# Sheet_FS8626.net
KiCad netlist of a schematic drawn in Altium Designer
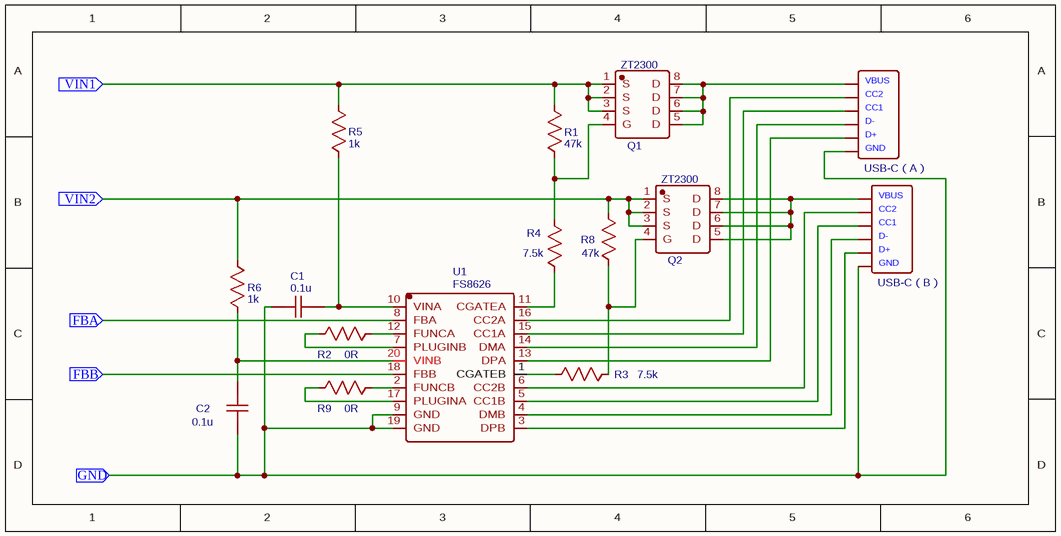
[diagram p0: Sheet_FS8626.schdoc]

(export (version "E")
  (design (tool "Eeschema 10.0.6"))
  (components
    (comp (ref "C1")
      (value "0.1u")
      (footprint "C0603")
      (fields (field (name "CONTRIBUTOR") "LCEDA_Lib"))
      (libsource (lib "altium-import") (part "root_0_0.1u_"))
    )
    (comp (ref "C2")
      (value "0.1u")
      (footprint "C0603")
      (fields (field (name "CONTRIBUTOR") "LCEDA_Lib"))
      (libsource (lib "altium-import") (part "root_1_0.1u_"))
    )
    (comp (ref "Q1")
      (value "ZT2300")
      (footprint "DFN3X3-8L")
      (fields
        (field (name "MANUFACTURER") "VBsemi Elec")
        (field (name "MANUFACTURER PART") "NCE3035G")
        (field (name "CONTRIBUTOR") "LCSC")
      )
      (libsource (lib "altium-import") (part "root_0_ZT2300_"))
    )
    (comp (ref "Q2")
      (value "ZT2300")
      (footprint "DFN3X3-8L")
      (fields
        (field (name "MANUFACTURER") "VBsemi Elec")
        (field (name "MANUFACTURER PART") "NCE3035G")
        (field (name "CONTRIBUTOR") "LCSC")
      )
      (libsource (lib "altium-import") (part "root_0_ZT2300_"))
    )
    (comp (ref "R1")
      (value "47k")
      (footprint "R0603")
      (fields (field (name "CONTRIBUTOR") "LCEDA_Lib"))
      (libsource (lib "altium-import") (part "root_1_47k_"))
    )
    (comp (ref "R2")
      (value "0R")
      (footprint "R0603")
      (fields (field (name "CONTRIBUTOR") "LCEDA_Lib"))
      (libsource (lib "altium-import") (part "root_0_0R_"))
    )
    (comp (ref "R3")
      (value "7.5k")
      (footprint "R0603")
      (fields (field (name "CONTRIBUTOR") "LCEDA_Lib"))
      (libsource (lib "altium-import") (part "root_0_7.5k_"))
    )
    (comp (ref "R4")
      (value "7.5k")
      (footprint "R0603")
      (fields (field (name "CONTRIBUTOR") "LCEDA_Lib"))
      (libsource (lib "altium-import") (part "root_1_7.5k_"))
    )
    (comp (ref "R5")
      (value "1k")
      (footprint "R1206")
      (fields (field (name "CONTRIBUTOR") "LCEDA_Lib"))
      (libsource (lib "altium-import") (part "root_1_1k_"))
    )
    (comp (ref "R6")
      (value "1k")
      (footprint "R1206")
      (fields (field (name "CONTRIBUTOR") "LCEDA_Lib"))
      (libsource (lib "altium-import") (part "root_1_1k_"))
    )
    (comp (ref "R8")
      (value "47k")
      (footprint "R0603")
      (fields (field (name "CONTRIBUTOR") "LCEDA_Lib"))
      (libsource (lib "altium-import") (part "root_1_47k_"))
    )
    (comp (ref "R9")
      (value "0R")
      (footprint "R0603")
      (fields (field (name "CONTRIBUTOR") "LCEDA_Lib"))
      (libsource (lib "altium-import") (part "root_0_0R_"))
    )
    (comp (ref "U1")
      (value "FS8626")
      (footprint "ETSSOP20_L6.5-W4.4-P0.65-LS6.4-BL")
      (fields
        (field (name "MANUFACTURER") "TI(德州仪器)")
        (field (name "MANUFACTURER PART") "PCF8574APWR")
        (field (name "CONTRIBUTOR") "LCSC")
      )
      (libsource (lib "altium-import") (part "root_0_FS8626_"))
    )
    (comp (ref "U2")
      (value "USB-C（B）")
      (footprint "FCQFN-15L_L3.0-W3.0-P0.50-BL_SCT63140FMAR")
      (fields
        (field (name "MANUFACTURER") "SCT")
        (field (name "MANUFACTURER PART") "SCT63140FMAR")
        (field (name "CONTRIBUTOR") "TaoPatrick")
      )
      (libsource (lib "altium-import") (part "root_0_USB-C（B）_"))
    )
    (comp (ref "U3")
      (value "USB-C（A）")
      (footprint "FCQFN-15L_L3.0-W3.0-P0.50-BL_SCT63140FMAR")
      (fields
        (field (name "MANUFACTURER") "SCT")
        (field (name "MANUFACTURER PART") "SCT63140FMAR")
        (field (name "CONTRIBUTOR") "TaoPatrick")
      )
      (libsource (lib "altium-import") (part "root_0_USB-C（A）_"))
    )
  )
  (nets
    (net (code "1") (name "/FBA") (class "Default")
      (node (ref "U1") (pin "8") (pinfunction "FBA_8") (pintype "passive"))
    )
    (net (code "2") (name "/FBB") (class "Default")
      (node (ref "U1") (pin "18") (pinfunction "FBB_18") (pintype "passive"))
    )
    (net (code "3") (name "/GND") (class "Default")
      (node (ref "C1") (pin "1") (pinfunction "1_1") (pintype "passive"))
      (node (ref "C2") (pin "1") (pinfunction "1_1") (pintype "passive"))
      (node (ref "U1") (pin "19") (pinfunction "GND_19") (pintype "passive"))
      (node (ref "U1") (pin "9") (pinfunction "GND_9") (pintype "passive"))
    )
    (net (code "4") (name "/VIN1") (class "Default")
      (node (ref "Q1") (pin "1") (pinfunction "S_1") (pintype "passive"))
      (node (ref "Q1") (pin "2") (pinfunction "S_2") (pintype "passive"))
      (node (ref "Q1") (pin "3") (pinfunction "S_3") (pintype "passive"))
      (node (ref "R1") (pin "2") (pinfunction "2_2") (pintype "passive"))
      (node (ref "R5") (pin "2") (pinfunction "2_2") (pintype "passive"))
    )
    (net (code "5") (name "/VIN2") (class "Default")
      (node (ref "Q2") (pin "1") (pinfunction "S_1") (pintype "passive"))
      (node (ref "Q2") (pin "2") (pinfunction "S_2") (pintype "passive"))
      (node (ref "Q2") (pin "3") (pinfunction "S_3") (pintype "passive"))
      (node (ref "R6") (pin "2") (pinfunction "2_2") (pintype "passive"))
      (node (ref "R8") (pin "2") (pinfunction "2_2") (pintype "passive"))
    )
    (net (code "6") (name "Net-(Q1-D-Pad5)") (class "Default")
      (node (ref "Q1") (pin "5") (pinfunction "D_5") (pintype "passive"))
      (node (ref "Q1") (pin "6") (pinfunction "D_6") (pintype "passive"))
      (node (ref "Q1") (pin "7") (pinfunction "D_7") (pintype "passive"))
      (node (ref "Q1") (pin "8") (pinfunction "D_8") (pintype "passive"))
    )
    (net (code "7") (name "Net-(Q1-G)") (class "Default")
      (node (ref "Q1") (pin "4") (pinfunction "G_4") (pintype "passive"))
      (node (ref "R1") (pin "1") (pinfunction "1_1") (pintype "passive"))
      (node (ref "R4") (pin "2") (pinfunction "2_2") (pintype "passive"))
    )
    (net (code "8") (name "Net-(Q2-D-Pad5)") (class "Default")
      (node (ref "Q2") (pin "5") (pinfunction "D_5") (pintype "passive"))
      (node (ref "Q2") (pin "6") (pinfunction "D_6") (pintype "passive"))
      (node (ref "Q2") (pin "7") (pinfunction "D_7") (pintype "passive"))
      (node (ref "Q2") (pin "8") (pinfunction "D_8") (pintype "passive"))
    )
    (net (code "9") (name "Net-(Q2-G)") (class "Default")
      (node (ref "Q2") (pin "4") (pinfunction "G_4") (pintype "passive"))
      (node (ref "R3") (pin "2") (pinfunction "2_2") (pintype "passive"))
      (node (ref "R8") (pin "1") (pinfunction "1_1") (pintype "passive"))
    )
    (net (code "10") (name "Net-(U1-CGATEA)") (class "Default")
      (node (ref "R4") (pin "1") (pinfunction "1_1") (pintype "passive"))
      (node (ref "U1") (pin "11") (pinfunction "CGATEA_11") (pintype "passive"))
    )
    (net (code "11") (name "Net-(U1-CGATEB)") (class "Default")
      (node (ref "R3") (pin "1") (pinfunction "1_1") (pintype "passive"))
      (node (ref "U1") (pin "1") (pinfunction "CGATEB_1") (pintype "passive"))
    )
    (net (code "12") (name "Net-(U1-FUNCA)") (class "Default")
      (node (ref "R2") (pin "2") (pinfunction "2_2") (pintype "passive"))
      (node (ref "U1") (pin "12") (pinfunction "FUNCA_12") (pintype "passive"))
    )
    (net (code "13") (name "Net-(U1-FUNCB)") (class "Default")
      (node (ref "R9") (pin "2") (pinfunction "2_2") (pintype "passive"))
      (node (ref "U1") (pin "2") (pinfunction "FUNCB_2") (pintype "passive"))
    )
    (net (code "14") (name "Net-(U1-PLUGINA)") (class "Default")
      (node (ref "R9") (pin "1") (pinfunction "1_1") (pintype "passive"))
      (node (ref "U1") (pin "17") (pinfunction "PLUGINA_17") (pintype "passive"))
    )
    (net (code "15") (name "Net-(U1-PLUGINB)") (class "Default")
      (node (ref "R2") (pin "1") (pinfunction "1_1") (pintype "passive"))
      (node (ref "U1") (pin "7") (pinfunction "PLUGINB_7") (pintype "passive"))
    )
    (net (code "16") (name "Net-(U1-VINA)") (class "Default")
      (node (ref "C1") (pin "2") (pinfunction "2_2") (pintype "passive"))
      (node (ref "R5") (pin "1") (pinfunction "1_1") (pintype "passive"))
      (node (ref "U1") (pin "10") (pinfunction "VINA_10") (pintype "passive"))
    )
    (net (code "17") (name "Net-(U1-VINB)") (class "Default")
      (node (ref "C2") (pin "2") (pinfunction "2_2") (pintype "passive"))
      (node (ref "R6") (pin "1") (pinfunction "1_1") (pintype "passive"))
      (node (ref "U1") (pin "20") (pinfunction "VINB_20") (pintype "passive"))
    )
    (net (code "18") (name "unconnected-(U1-CC1A-Pad15)") (class "Default")
      (node (ref "U1") (pin "15") (pinfunction "CC1A_15") (pintype "passive"))
    )
    (net (code "19") (name "unconnected-(U1-CC1B-Pad5)") (class "Default")
      (node (ref "U1") (pin "5") (pinfunction "CC1B_5") (pintype "passive"))
    )
    (net (code "20") (name "unconnected-(U1-CC2A-Pad16)") (class "Default")
      (node (ref "U1") (pin "16") (pinfunction "CC2A_16") (pintype "passive"))
    )
    (net (code "21") (name "unconnected-(U1-CC2B-Pad6)") (class "Default")
      (node (ref "U1") (pin "6") (pinfunction "CC2B_6") (pintype "passive"))
    )
    (net (code "22") (name "unconnected-(U1-DMA-Pad14)") (class "Default")
      (node (ref "U1") (pin "14") (pinfunction "DMA_14") (pintype "passive"))
    )
    (net (code "23") (name "unconnected-(U1-DMB-Pad4)") (class "Default")
      (node (ref "U1") (pin "4") (pinfunction "DMB_4") (pintype "passive"))
    )
    (net (code "24") (name "unconnected-(U1-DPA-Pad13)") (class "Default")
      (node (ref "U1") (pin "13") (pinfunction "DPA_13") (pintype "passive"))
    )
    (net (code "25") (name "unconnected-(U1-DPB-Pad3)") (class "Default")
      (node (ref "U1") (pin "3") (pinfunction "DPB_3") (pintype "passive"))
    )
    (net (code "26") (name "unconnected-(U2-SHELD-Pad2)") (class "Default")
      (node (ref "U2") (pin "2") (pinfunction "SHELD_2") (pintype "passive"))
    )
    (net (code "27") (name "unconnected-(U2-SHELD-Pad3)") (class "Default")
      (node (ref "U2") (pin "3") (pinfunction "SHELD_3") (pintype "passive"))
    )
    (net (code "28") (name "unconnected-(U2-SHELD-Pad4)") (class "Default")
      (node (ref "U2") (pin "4") (pinfunction "SHELD_4") (pintype "passive"))
    )
    (net (code "29") (name "unconnected-(U2-SHELD-Pad5)") (class "Default")
      (node (ref "U2") (pin "5") (pinfunction "SHELD_5") (pintype "passive"))
    )
    (net (code "30") (name "unconnected-(U2-SHELD-Pad5)_1") (class "Default")
      (node (ref "U2") (pin "5") (pinfunction "SHELD_5") (pintype "passive"))
    )
    (net (code "31") (name "unconnected-(U2-SHELD-Pad6)") (class "Default")
      (node (ref "U2") (pin "6") (pinfunction "SHELD_6") (pintype "passive"))
    )
    (net (code "32") (name "unconnected-(U3-SHELD-Pad2)") (class "Default")
      (node (ref "U3") (pin "2") (pinfunction "SHELD_2") (pintype "passive"))
    )
    (net (code "33") (name "unconnected-(U3-SHELD-Pad3)") (class "Default")
      (node (ref "U3") (pin "3") (pinfunction "SHELD_3") (pintype "passive"))
    )
    (net (code "34") (name "unconnected-(U3-SHELD-Pad4)") (class "Default")
      (node (ref "U3") (pin "4") (pinfunction "SHELD_4") (pintype "passive"))
    )
    (net (code "35") (name "unconnected-(U3-SHELD-Pad5)") (class "Default")
      (node (ref "U3") (pin "5") (pinfunction "SHELD_5") (pintype "passive"))
    )
    (net (code "36") (name "unconnected-(U3-SHELD-Pad5)_1") (class "Default")
      (node (ref "U3") (pin "5") (pinfunction "SHELD_5") (pintype "passive"))
    )
    (net (code "37") (name "unconnected-(U3-SHELD-Pad6)") (class "Default")
      (node (ref "U3") (pin "6") (pinfunction "SHELD_6") (pintype "passive"))
    )
  )
)
